# throughhole.net
KiCad netlist of a schematic drawn in EAGLE
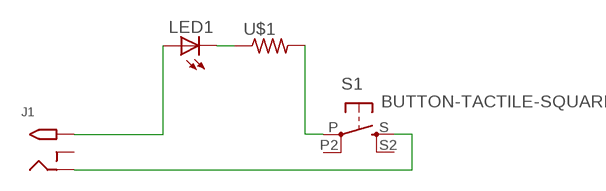
[diagram p0: schematic, sheet 1]

(export (version "E")
  (design (tool "Eeschema 10.0.6"))
  (components
    (comp (ref "J1")
      (value "2.1MMJACKTHM")
      (footprint "eagle-import:PJ-102A")
      (libsource (lib "eagle-import") (part "2.1MMJACKTHM"))
    )
    (comp (ref "LED1")
      (value "LED5MM")
      (footprint "eagle-import:LED5MM")
      (libsource (lib "eagle-import") (part "LED5MM"))
    )
    (comp (ref "S1")
      (value "BUTTON-TACTILE-SQUARE")
      (footprint "eagle-import:BUTTON-TACTILE-SQUARE-ADAFRUIT1010")
      (libsource (lib "eagle-import") (part "BUTTON-TACTILE-SQUARE"))
    )
    (comp (ref "U$1")
      (value "RESISTORTH-1/4W-CARBON")
      (footprint "eagle-import:RESAD1160W55L680D260_HS")
      (libsource (lib "eagle-import") (part "RESISTORTH-1/4W-CARBON"))
    )
  )
  (nets
    (net (code "1") (name "Net-(J1-PadRING)") (class "Default")
      (node (ref "J1") (pin "RING") (pinfunction "RING_RING") (pintype "bidirectional"))
      (node (ref "S1") (pin "S") (pinfunction "S_S") (pintype "passive"))
    )
    (net (code "2") (name "Net-(J1-PadTIP)") (class "Default")
      (node (ref "J1") (pin "TIP") (pinfunction "TIP_TIP") (pintype "bidirectional"))
      (node (ref "LED1") (pin "A") (pinfunction "A_A") (pintype "passive"))
    )
    (net (code "3") (name "Net-(LED1-C)") (class "Default")
      (node (ref "LED1") (pin "K") (pinfunction "C_K") (pintype "passive"))
      (node (ref "U$1") (pin "1") (pinfunction "1_1") (pintype "passive"))
    )
    (net (code "4") (name "Net-(S1-PadP)") (class "Default")
      (node (ref "S1") (pin "P") (pinfunction "P_P") (pintype "passive"))
      (node (ref "U$1") (pin "2") (pinfunction "2_2") (pintype "passive"))
    )
    (net (code "5") (name "unconnected-(J1-PadRING_SW)") (class "Default")
      (node (ref "J1") (pin "RING_SW") (pinfunction "RING_SW_RING_SW") (pintype "bidirectional"))
    )
    (net (code "6") (name "unconnected-(S1-P1-PadP2)") (class "Default")
      (node (ref "S1") (pin "P2") (pinfunction "P1_P2") (pintype "passive"))
    )
    (net (code "7") (name "unconnected-(S1-S1-PadS2)") (class "Default")
      (node (ref "S1") (pin "S2") (pinfunction "S1_S2") (pintype "passive"))
    )
  )
)
